# GSIOC.net
KiCad netlist of a schematic drawn in EAGLE
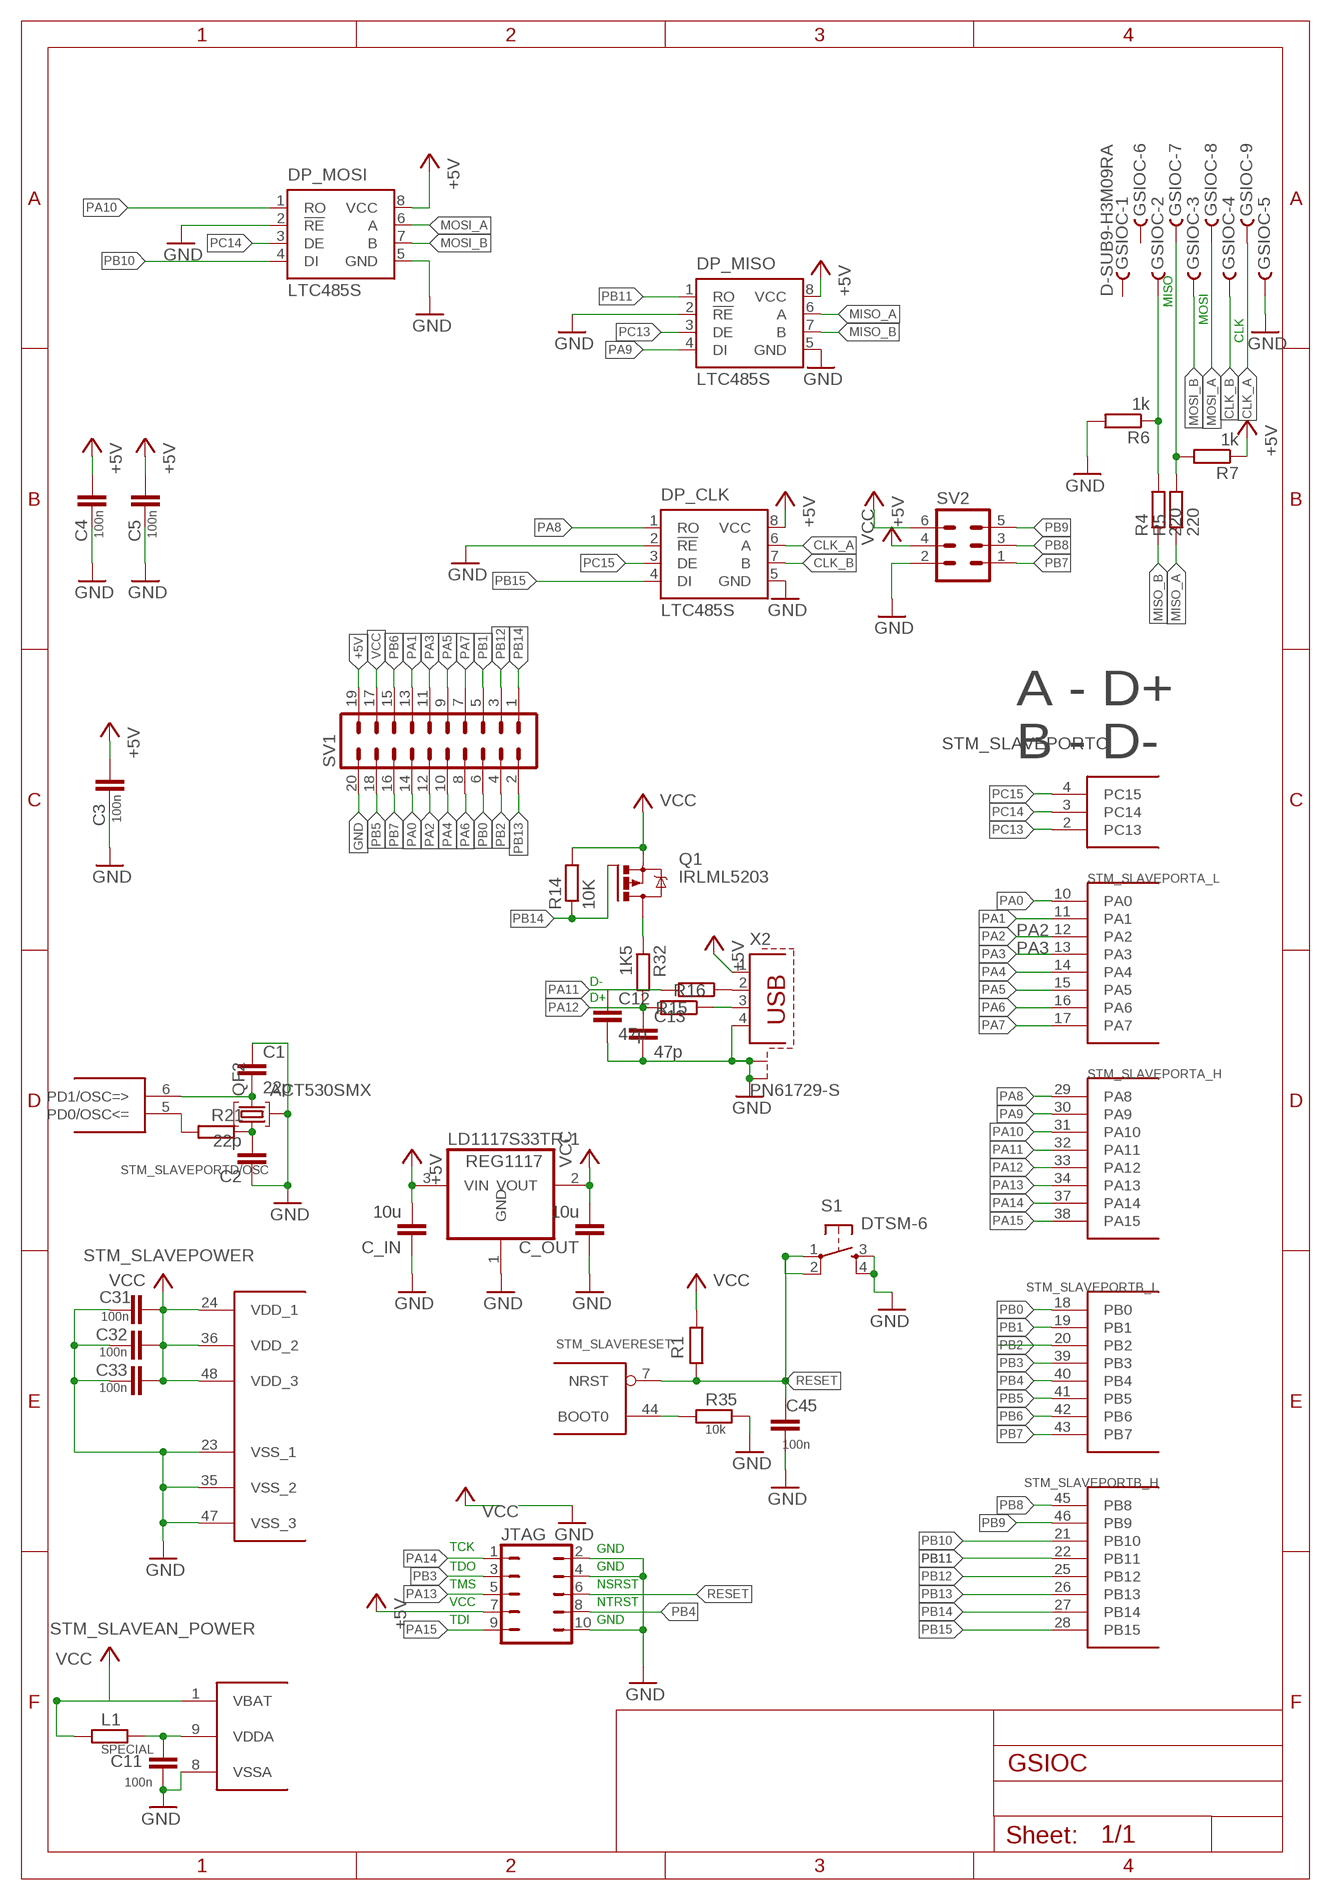
[diagram p0: schematic, sheet 1]

(export (version "E")
  (design (tool "Eeschema 10.0.6"))
  (components
    (comp (ref "C1")
      (value "22p")
      (footprint "eagle-import:C0805")
      (libsource (lib "eagle-import") (part "resistor_C-EUC0805"))
    )
    (comp (ref "C2")
      (value "22p")
      (footprint "eagle-import:C0805")
      (libsource (lib "eagle-import") (part "resistor_C-EUC0805"))
    )
    (comp (ref "C3")
      (value "100n")
      (footprint "eagle-import:C0805")
      (libsource (lib "eagle-import") (part "resistor_C-EUC0805"))
    )
    (comp (ref "C4")
      (value "100n")
      (footprint "eagle-import:C0805K")
      (libsource (lib "eagle-import") (part "C-EUC0805K"))
    )
    (comp (ref "C5")
      (value "100n")
      (footprint "eagle-import:C0805K")
      (libsource (lib "eagle-import") (part "C-EUC0805K"))
    )
    (comp (ref "C11")
      (value "100n")
      (footprint "eagle-import:C0805")
      (libsource (lib "eagle-import") (part "resistor_C-EUC0805"))
    )
    (comp (ref "C12")
      (value "47p")
      (footprint "eagle-import:C0805K")
      (libsource (lib "eagle-import") (part "C-EUC0805K"))
    )
    (comp (ref "C13")
      (value "47p")
      (footprint "eagle-import:C0805K")
      (libsource (lib "eagle-import") (part "C-EUC0805K"))
    )
    (comp (ref "C31")
      (value "100n")
      (footprint "eagle-import:C0805")
      (libsource (lib "eagle-import") (part "resistor_C-EUC0805"))
    )
    (comp (ref "C32")
      (value "100n")
      (footprint "eagle-import:C0805")
      (libsource (lib "eagle-import") (part "resistor_C-EUC0805"))
    )
    (comp (ref "C33")
      (value "100n")
      (footprint "eagle-import:C0805")
      (libsource (lib "eagle-import") (part "resistor_C-EUC0805"))
    )
    (comp (ref "C45")
      (value "100n")
      (footprint "eagle-import:C0805K")
      (libsource (lib "eagle-import") (part "C-EUC0805K"))
    )
    (comp (ref "C_IN")
      (value "10u")
      (footprint "eagle-import:C0805K")
      (libsource (lib "eagle-import") (part "C-EUC0805K"))
    )
    (comp (ref "C_OUT")
      (value "10u")
      (footprint "eagle-import:C0805K")
      (libsource (lib "eagle-import") (part "C-EUC0805K"))
    )
    (comp (ref "DP_CLK")
      (value "LTC485S")
      (footprint "eagle-import:SOIC8")
      (libsource (lib "eagle-import") (part "LTC485S"))
    )
    (comp (ref "DP_MISO")
      (value "LTC485S")
      (footprint "eagle-import:SOIC8")
      (libsource (lib "eagle-import") (part "LTC485S"))
    )
    (comp (ref "DP_MOSI")
      (value "LTC485S")
      (footprint "eagle-import:SOIC8")
      (libsource (lib "eagle-import") (part "LTC485S"))
    )
    (comp (ref "GSIOC")
      (value "D-SUB9-H3M09RA")
      (footprint "eagle-import:H3M09RA")
      (libsource (lib "eagle-import") (part "D-SUB9-H3M09RA"))
    )
    (comp (ref "JTAG")
      (value "JP5Q")
      (footprint "eagle-import:JP5Q")
      (libsource (lib "eagle-import") (part "JP5Q"))
    )
    (comp (ref "L1")
      (value "SPECIAL")
      (footprint "eagle-import:M0805")
      (libsource (lib "eagle-import") (part "R-EU_M0805"))
    )
    (comp (ref "LD1117S33TR-1")
      (value "REG1117")
      (footprint "eagle-import:SOT223")
      (libsource (lib "eagle-import") (part "REG1117"))
    )
    (comp (ref "Q1")
      (value "IRLML5203")
      (footprint "eagle-import:MICRO3")
      (libsource (lib "eagle-import") (part "IRLML5203"))
    )
    (comp (ref "QF2")
      (value "ACT530SMX")
      (footprint "eagle-import:ACT_530SMX")
      (libsource (lib "eagle-import") (part "ACT530SMX"))
    )
    (comp (ref "R1")
      (value "5k")
      (footprint "eagle-import:M0805")
      (libsource (lib "eagle-import") (part "R-EU_M0805"))
    )
    (comp (ref "R4")
      (value "220")
      (footprint "eagle-import:M0805")
      (libsource (lib "eagle-import") (part "R-EU_M0805"))
    )
    (comp (ref "R5")
      (value "220")
      (footprint "eagle-import:M0805")
      (libsource (lib "eagle-import") (part "R-EU_M0805"))
    )
    (comp (ref "R6")
      (value "1k")
      (footprint "eagle-import:M0805")
      (libsource (lib "eagle-import") (part "R-EU_M0805"))
    )
    (comp (ref "R7")
      (value "1k")
      (footprint "eagle-import:M0805")
      (libsource (lib "eagle-import") (part "R-EU_M0805"))
    )
    (comp (ref "R14")
      (value "10K")
      (footprint "eagle-import:M0805")
      (libsource (lib "eagle-import") (part "R-EU_M0805"))
    )
    (comp (ref "R15")
      (value "22")
      (footprint "eagle-import:M0805")
      (libsource (lib "eagle-import") (part "R-EU_M0805"))
    )
    (comp (ref "R16")
      (value "22")
      (footprint "eagle-import:M0805")
      (libsource (lib "eagle-import") (part "R-EU_M0805"))
    )
    (comp (ref "R21")
      (value "R-EU_M0805")
      (footprint "eagle-import:M0805")
      (libsource (lib "eagle-import") (part "R-EU_M0805"))
    )
    (comp (ref "R32")
      (value "1K5")
      (footprint "eagle-import:M0805")
      (libsource (lib "eagle-import") (part "R-EU_M0805"))
    )
    (comp (ref "R35")
      (value "10k")
      (footprint "eagle-import:M0805")
      (libsource (lib "eagle-import") (part "R-EU_M0805"))
    )
    (comp (ref "S1")
      (value "DTSM-6")
      (footprint "eagle-import:DTSM-6")
      (libsource (lib "eagle-import") (part "DTSM-6"))
    )
    (comp (ref "STM_SLAVE")
      (value "STM32F10XCXT6")
      (footprint "eagle-import:TQFP48")
      (libsource (lib "eagle-import") (part "STM32F10XCXT6"))
    )
    (comp (ref "SV1")
      (value "ML20L")
      (footprint "eagle-import:ML20L")
      (libsource (lib "eagle-import") (part "ML20L"))
    )
    (comp (ref "SV2")
      (value "ML6L")
      (footprint "eagle-import:ML6L")
      (libsource (lib "eagle-import") (part "ML6L"))
    )
    (comp (ref "X2")
      (value "PN61729-S")
      (footprint "eagle-import:PN61729-S")
      (libsource (lib "eagle-import") (part "PN61729-S"))
    )
  )
  (nets
    (net (code "1") (name "+5V") (class "Default")
      (node (ref "C3") (pin "1") (pinfunction "1_1") (pintype "passive"))
      (node (ref "C4") (pin "1") (pinfunction "1_1") (pintype "passive"))
      (node (ref "C5") (pin "1") (pinfunction "1_1") (pintype "passive"))
      (node (ref "C_IN") (pin "2") (pinfunction "2_2") (pintype "passive"))
      (node (ref "DP_CLK") (pin "8") (pinfunction "VCC_8") (pintype "input"))
      (node (ref "DP_MISO") (pin "8") (pinfunction "VCC_8") (pintype "input"))
      (node (ref "DP_MOSI") (pin "8") (pinfunction "VCC_8") (pintype "input"))
      (node (ref "JTAG") (pin "7") (pinfunction "7_7") (pintype "passive"))
      (node (ref "LD1117S33TR-1") (pin "3") (pinfunction "VIN_3") (pintype "input"))
      (node (ref "R7") (pin "1") (pinfunction "1_1") (pintype "passive"))
      (node (ref "SV1") (pin "19") (pinfunction "19_19") (pintype "passive"))
      (node (ref "SV2") (pin "6") (pinfunction "6_6") (pintype "passive"))
      (node (ref "X2") (pin "1") (pinfunction "1_1") (pintype "passive"))
    )
    (net (code "2") (name "CLK_A") (class "Default")
      (node (ref "DP_CLK") (pin "6") (pinfunction "A_6") (pintype "bidirectional"))
      (node (ref "GSIOC") (pin "9") (pinfunction "F_9") (pintype "passive"))
    )
    (net (code "3") (name "CLK_B") (class "Default")
      (node (ref "DP_CLK") (pin "7") (pinfunction "B_7") (pintype "bidirectional"))
      (node (ref "GSIOC") (pin "4") (pinfunction "F_4") (pintype "passive"))
    )
    (net (code "4") (name "GND") (class "Default")
      (node (ref "C1") (pin "1") (pinfunction "1_1") (pintype "passive"))
      (node (ref "C11") (pin "2") (pinfunction "2_2") (pintype "passive"))
      (node (ref "C12") (pin "2") (pinfunction "2_2") (pintype "passive"))
      (node (ref "C13") (pin "2") (pinfunction "2_2") (pintype "passive"))
      (node (ref "C2") (pin "1") (pinfunction "1_1") (pintype "passive"))
      (node (ref "C3") (pin "2") (pinfunction "2_2") (pintype "passive"))
      (node (ref "C31") (pin "2") (pinfunction "2_2") (pintype "passive"))
      (node (ref "C32") (pin "2") (pinfunction "2_2") (pintype "passive"))
      (node (ref "C33") (pin "2") (pinfunction "2_2") (pintype "passive"))
      (node (ref "C4") (pin "2") (pinfunction "2_2") (pintype "passive"))
      (node (ref "C45") (pin "2") (pinfunction "2_2") (pintype "passive"))
      (node (ref "C5") (pin "2") (pinfunction "2_2") (pintype "passive"))
      (node (ref "C_IN") (pin "1") (pinfunction "1_1") (pintype "passive"))
      (node (ref "C_OUT") (pin "1") (pinfunction "1_1") (pintype "passive"))
      (node (ref "DP_CLK") (pin "2") (pinfunction "~{RE}_2") (pintype "input"))
      (node (ref "DP_CLK") (pin "5") (pinfunction "GND_5") (pintype "input"))
      (node (ref "DP_MISO") (pin "2") (pinfunction "~{RE}_2") (pintype "input"))
      (node (ref "DP_MISO") (pin "5") (pinfunction "GND_5") (pintype "input"))
      (node (ref "DP_MOSI") (pin "2") (pinfunction "~{RE}_2") (pintype "input"))
      (node (ref "DP_MOSI") (pin "5") (pinfunction "GND_5") (pintype "input"))
      (node (ref "GSIOC") (pin "5") (pinfunction "F_5") (pintype "passive"))
      (node (ref "JTAG") (pin "10") (pinfunction "10_10") (pintype "passive"))
      (node (ref "JTAG") (pin "2") (pinfunction "2_2") (pintype "passive"))
      (node (ref "JTAG") (pin "4") (pinfunction "4_4") (pintype "passive"))
      (node (ref "LD1117S33TR-1") (pin "1") (pinfunction "GND_1") (pintype "power_in"))
      (node (ref "QF2") (pin "S$1") (pinfunction "SHLD_S$1") (pintype "passive"))
      (node (ref "QF2") (pin "S$2") (pinfunction "SHLD_S$2") (pintype "passive"))
      (node (ref "R35") (pin "2") (pinfunction "2_2") (pintype "passive"))
      (node (ref "R6") (pin "2") (pinfunction "2_2") (pintype "passive"))
      (node (ref "S1") (pin "3") (pinfunction "3_3") (pintype "passive"))
      (node (ref "S1") (pin "4") (pinfunction "4_4") (pintype "passive"))
      (node (ref "STM_SLAVE") (pin "23") (pinfunction "VSS_1_23") (pintype "power_in"))
      (node (ref "STM_SLAVE") (pin "35") (pinfunction "VSS_2_35") (pintype "power_in"))
      (node (ref "STM_SLAVE") (pin "47") (pinfunction "VSS_3_47") (pintype "power_in"))
      (node (ref "STM_SLAVE") (pin "8") (pinfunction "VSSA_8") (pintype "power_in"))
      (node (ref "SV1") (pin "20") (pinfunction "20_20") (pintype "passive"))
      (node (ref "SV2") (pin "2") (pinfunction "2_2") (pintype "passive"))
      (node (ref "X2") (pin "4") (pinfunction "4_4") (pintype "passive"))
      (node (ref "X2") (pin "S1") (pinfunction "S1_S1") (pintype "passive"))
      (node (ref "X2") (pin "S2") (pinfunction "S2_S2") (pintype "passive"))
    )
    (net (code "5") (name "MISO_A") (class "Default")
      (node (ref "DP_MISO") (pin "6") (pinfunction "A_6") (pintype "bidirectional"))
      (node (ref "R5") (pin "1") (pinfunction "1_1") (pintype "passive"))
    )
    (net (code "6") (name "MISO_B") (class "Default")
      (node (ref "DP_MISO") (pin "7") (pinfunction "B_7") (pintype "bidirectional"))
      (node (ref "R4") (pin "1") (pinfunction "1_1") (pintype "passive"))
    )
    (net (code "7") (name "MOSI_A") (class "Default")
      (node (ref "DP_MOSI") (pin "6") (pinfunction "A_6") (pintype "bidirectional"))
      (node (ref "GSIOC") (pin "8") (pinfunction "F_8") (pintype "passive"))
    )
    (net (code "8") (name "MOSI_B") (class "Default")
      (node (ref "DP_MOSI") (pin "7") (pinfunction "B_7") (pintype "bidirectional"))
      (node (ref "GSIOC") (pin "3") (pinfunction "F_3") (pintype "passive"))
    )
    (net (code "9") (name "Net-(GSIOCB-F)") (class "Default")
      (node (ref "GSIOC") (pin "2") (pinfunction "F_2") (pintype "passive"))
      (node (ref "R4") (pin "2") (pinfunction "2_2") (pintype "passive"))
      (node (ref "R6") (pin "1") (pinfunction "1_1") (pintype "passive"))
    )
    (net (code "10") (name "Net-(GSIOCG-F)") (class "Default")
      (node (ref "GSIOC") (pin "7") (pinfunction "F_7") (pintype "passive"))
      (node (ref "R5") (pin "2") (pinfunction "2_2") (pintype "passive"))
      (node (ref "R7") (pin "2") (pinfunction "2_2") (pintype "passive"))
    )
    (net (code "11") (name "Net-(Q1-D)") (class "Default")
      (node (ref "Q1") (pin "3") (pinfunction "D_3") (pintype "passive"))
      (node (ref "R32") (pin "1") (pinfunction "1_1") (pintype "passive"))
    )
    (net (code "12") (name "Net-(QF2-1)") (class "Default")
      (node (ref "C2") (pin "2") (pinfunction "2_2") (pintype "passive"))
      (node (ref "QF2") (pin "P1") (pinfunction "1_P1") (pintype "passive"))
      (node (ref "R21") (pin "1") (pinfunction "1_1") (pintype "passive"))
    )
    (net (code "13") (name "Net-(QF2-2)") (class "Default")
      (node (ref "C1") (pin "2") (pinfunction "2_2") (pintype "passive"))
      (node (ref "QF2") (pin "P2") (pinfunction "2_P2") (pintype "passive"))
      (node (ref "STM_SLAVE") (pin "6") (pinfunction "PD1/OSC=>_6") (pintype "bidirectional"))
    )
    (net (code "14") (name "Net-(R15-Pad1)") (class "Default")
      (node (ref "R15") (pin "1") (pinfunction "1_1") (pintype "passive"))
      (node (ref "X2") (pin "3") (pinfunction "3_3") (pintype "passive"))
    )
    (net (code "15") (name "Net-(R16-Pad1)") (class "Default")
      (node (ref "R16") (pin "1") (pinfunction "1_1") (pintype "passive"))
      (node (ref "X2") (pin "2") (pinfunction "2_2") (pintype "passive"))
    )
    (net (code "16") (name "Net-(STM_SLAVEA-VDDA)") (class "Default")
      (node (ref "C11") (pin "1") (pinfunction "1_1") (pintype "passive"))
      (node (ref "L1") (pin "2") (pinfunction "2_2") (pintype "passive"))
      (node (ref "STM_SLAVE") (pin "9") (pinfunction "VDDA_9") (pintype "power_in"))
    )
    (net (code "17") (name "Net-(STM_SLAVEG-PD0{slash}OSC<=)") (class "Default")
      (node (ref "R21") (pin "2") (pinfunction "2_2") (pintype "passive"))
      (node (ref "STM_SLAVE") (pin "5") (pinfunction "PD0/OSC<=_5") (pintype "bidirectional"))
    )
    (net (code "18") (name "Net-(STM_SLAVEI-BOOT0)") (class "Default")
      (node (ref "R35") (pin "1") (pinfunction "1_1") (pintype "passive"))
      (node (ref "STM_SLAVE") (pin "44") (pinfunction "BOOT0_44") (pintype "input"))
    )
    (net (code "19") (name "PA0") (class "Default")
      (node (ref "STM_SLAVE") (pin "10") (pinfunction "PA0_10") (pintype "bidirectional"))
      (node (ref "SV1") (pin "14") (pinfunction "14_14") (pintype "passive"))
    )
    (net (code "20") (name "PA1") (class "Default")
      (node (ref "STM_SLAVE") (pin "11") (pinfunction "PA1_11") (pintype "bidirectional"))
      (node (ref "SV1") (pin "13") (pinfunction "13_13") (pintype "passive"))
    )
    (net (code "21") (name "PA2") (class "Default")
      (node (ref "STM_SLAVE") (pin "12") (pinfunction "PA2_12") (pintype "bidirectional"))
      (node (ref "SV1") (pin "12") (pinfunction "12_12") (pintype "passive"))
    )
    (net (code "22") (name "PA3") (class "Default")
      (node (ref "STM_SLAVE") (pin "13") (pinfunction "PA3_13") (pintype "bidirectional"))
      (node (ref "SV1") (pin "11") (pinfunction "11_11") (pintype "passive"))
    )
    (net (code "23") (name "PA4") (class "Default")
      (node (ref "STM_SLAVE") (pin "14") (pinfunction "PA4_14") (pintype "bidirectional"))
      (node (ref "SV1") (pin "10") (pinfunction "10_10") (pintype "passive"))
    )
    (net (code "24") (name "PA5") (class "Default")
      (node (ref "STM_SLAVE") (pin "15") (pinfunction "PA5_15") (pintype "bidirectional"))
      (node (ref "SV1") (pin "9") (pinfunction "9_9") (pintype "passive"))
    )
    (net (code "25") (name "PA6") (class "Default")
      (node (ref "STM_SLAVE") (pin "16") (pinfunction "PA6_16") (pintype "bidirectional"))
      (node (ref "SV1") (pin "8") (pinfunction "8_8") (pintype "passive"))
    )
    (net (code "26") (name "PA7") (class "Default")
      (node (ref "STM_SLAVE") (pin "17") (pinfunction "PA7_17") (pintype "bidirectional"))
      (node (ref "SV1") (pin "7") (pinfunction "7_7") (pintype "passive"))
    )
    (net (code "27") (name "PA8") (class "Default")
      (node (ref "DP_CLK") (pin "1") (pinfunction "RO_1") (pintype "output"))
      (node (ref "STM_SLAVE") (pin "29") (pinfunction "PA8_29") (pintype "bidirectional"))
    )
    (net (code "28") (name "PA9") (class "Default")
      (node (ref "DP_MISO") (pin "4") (pinfunction "DI_4") (pintype "input"))
      (node (ref "STM_SLAVE") (pin "30") (pinfunction "PA9_30") (pintype "bidirectional"))
    )
    (net (code "29") (name "PA10") (class "Default")
      (node (ref "DP_MOSI") (pin "1") (pinfunction "RO_1") (pintype "output"))
      (node (ref "STM_SLAVE") (pin "31") (pinfunction "PA10_31") (pintype "bidirectional"))
    )
    (net (code "30") (name "PA11") (class "Default")
      (node (ref "C12") (pin "1") (pinfunction "1_1") (pintype "passive"))
      (node (ref "R16") (pin "2") (pinfunction "2_2") (pintype "passive"))
      (node (ref "STM_SLAVE") (pin "32") (pinfunction "PA11_32") (pintype "bidirectional"))
    )
    (net (code "31") (name "PA12") (class "Default")
      (node (ref "C13") (pin "1") (pinfunction "1_1") (pintype "passive"))
      (node (ref "R15") (pin "2") (pinfunction "2_2") (pintype "passive"))
      (node (ref "R32") (pin "2") (pinfunction "2_2") (pintype "passive"))
      (node (ref "STM_SLAVE") (pin "33") (pinfunction "PA12_33") (pintype "bidirectional"))
    )
    (net (code "32") (name "PA13") (class "Default")
      (node (ref "JTAG") (pin "5") (pinfunction "5_5") (pintype "passive"))
      (node (ref "STM_SLAVE") (pin "34") (pinfunction "PA13_34") (pintype "bidirectional"))
    )
    (net (code "33") (name "PA14") (class "Default")
      (node (ref "JTAG") (pin "1") (pinfunction "1_1") (pintype "passive"))
      (node (ref "STM_SLAVE") (pin "37") (pinfunction "PA14_37") (pintype "bidirectional"))
    )
    (net (code "34") (name "PA15") (class "Default")
      (node (ref "JTAG") (pin "9") (pinfunction "9_9") (pintype "passive"))
      (node (ref "STM_SLAVE") (pin "38") (pinfunction "PA15_38") (pintype "bidirectional"))
    )
    (net (code "35") (name "PB0") (class "Default")
      (node (ref "STM_SLAVE") (pin "18") (pinfunction "PB0_18") (pintype "bidirectional"))
      (node (ref "SV1") (pin "6") (pinfunction "6_6") (pintype "passive"))
    )
    (net (code "36") (name "PB1") (class "Default")
      (node (ref "STM_SLAVE") (pin "19") (pinfunction "PB1_19") (pintype "bidirectional"))
      (node (ref "SV1") (pin "5") (pinfunction "5_5") (pintype "passive"))
    )
    (net (code "37") (name "PB2") (class "Default")
      (node (ref "STM_SLAVE") (pin "20") (pinfunction "PB2_20") (pintype "bidirectional"))
      (node (ref "SV1") (pin "4") (pinfunction "4_4") (pintype "passive"))
    )
    (net (code "38") (name "PB3") (class "Default")
      (node (ref "JTAG") (pin "3") (pinfunction "3_3") (pintype "passive"))
      (node (ref "STM_SLAVE") (pin "39") (pinfunction "PB3_39") (pintype "bidirectional"))
    )
    (net (code "39") (name "PB4") (class "Default")
      (node (ref "JTAG") (pin "8") (pinfunction "8_8") (pintype "passive"))
      (node (ref "STM_SLAVE") (pin "40") (pinfunction "PB4_40") (pintype "bidirectional"))
    )
    (net (code "40") (name "PB5") (class "Default")
      (node (ref "STM_SLAVE") (pin "41") (pinfunction "PB5_41") (pintype "bidirectional"))
      (node (ref "SV1") (pin "18") (pinfunction "18_18") (pintype "passive"))
    )
    (net (code "41") (name "PB6") (class "Default")
      (node (ref "STM_SLAVE") (pin "42") (pinfunction "PB6_42") (pintype "bidirectional"))
      (node (ref "SV1") (pin "15") (pinfunction "15_15") (pintype "passive"))
    )
    (net (code "42") (name "PB7") (class "Default")
      (node (ref "STM_SLAVE") (pin "43") (pinfunction "PB7_43") (pintype "bidirectional"))
      (node (ref "SV1") (pin "16") (pinfunction "16_16") (pintype "passive"))
      (node (ref "SV2") (pin "1") (pinfunction "1_1") (pintype "passive"))
    )
    (net (code "43") (name "PB8") (class "Default")
      (node (ref "STM_SLAVE") (pin "45") (pinfunction "PB8_45") (pintype "bidirectional"))
      (node (ref "SV2") (pin "3") (pinfunction "3_3") (pintype "passive"))
    )
    (net (code "44") (name "PB9") (class "Default")
      (node (ref "STM_SLAVE") (pin "46") (pinfunction "PB9_46") (pintype "bidirectional"))
      (node (ref "SV2") (pin "5") (pinfunction "5_5") (pintype "passive"))
    )
    (net (code "45") (name "PB10") (class "Default")
      (node (ref "DP_MOSI") (pin "4") (pinfunction "DI_4") (pintype "input"))
      (node (ref "STM_SLAVE") (pin "21") (pinfunction "PB10_21") (pintype "bidirectional"))
    )
    (net (code "46") (name "PB11") (class "Default")
      (node (ref "DP_MISO") (pin "1") (pinfunction "RO_1") (pintype "output"))
      (node (ref "STM_SLAVE") (pin "22") (pinfunction "PB11_22") (pintype "bidirectional"))
    )
    (net (code "47") (name "PB12") (class "Default")
      (node (ref "STM_SLAVE") (pin "25") (pinfunction "PB12_25") (pintype "bidirectional"))
      (node (ref "SV1") (pin "3") (pinfunction "3_3") (pintype "passive"))
    )
    (net (code "48") (name "PB13") (class "Default")
      (node (ref "STM_SLAVE") (pin "26") (pinfunction "PB13_26") (pintype "bidirectional"))
      (node (ref "SV1") (pin "2") (pinfunction "2_2") (pintype "passive"))
    )
    (net (code "49") (name "PB14") (class "Default")
      (node (ref "Q1") (pin "1") (pinfunction "G_1") (pintype "passive"))
      (node (ref "R14") (pin "1") (pinfunction "1_1") (pintype "passive"))
      (node (ref "STM_SLAVE") (pin "27") (pinfunction "PB14_27") (pintype "bidirectional"))
      (node (ref "SV1") (pin "1") (pinfunction "1_1") (pintype "passive"))
    )
    (net (code "50") (name "PB15") (class "Default")
      (node (ref "DP_CLK") (pin "4") (pinfunction "DI_4") (pintype "input"))
      (node (ref "STM_SLAVE") (pin "28") (pinfunction "PB15_28") (pintype "bidirectional"))
    )
    (net (code "51") (name "PC13") (class "Default")
      (node (ref "DP_MISO") (pin "3") (pinfunction "DE_3") (pintype "input"))
      (node (ref "STM_SLAVE") (pin "2") (pinfunction "PC13_2") (pintype "bidirectional"))
    )
    (net (code "52") (name "PC14") (class "Default")
      (node (ref "DP_MOSI") (pin "3") (pinfunction "DE_3") (pintype "input"))
      (node (ref "STM_SLAVE") (pin "3") (pinfunction "PC14_3") (pintype "bidirectional"))
    )
    (net (code "53") (name "PC15") (class "Default")
      (node (ref "DP_CLK") (pin "3") (pinfunction "DE_3") (pintype "input"))
      (node (ref "STM_SLAVE") (pin "4") (pinfunction "PC15_4") (pintype "bidirectional"))
    )
    (net (code "54") (name "RESET") (class "Default")
      (node (ref "C45") (pin "1") (pinfunction "1_1") (pintype "passive"))
      (node (ref "JTAG") (pin "6") (pinfunction "6_6") (pintype "passive"))
      (node (ref "R1") (pin "2") (pinfunction "2_2") (pintype "passive"))
      (node (ref "S1") (pin "1") (pinfunction "1_1") (pintype "passive"))
      (node (ref "S1") (pin "2") (pinfunction "2_2") (pintype "passive"))
      (node (ref "STM_SLAVE") (pin "7") (pinfunction "NRST_7") (pintype "input"))
    )
    (net (code "55") (name "VCC") (class "Default")
      (node (ref "C31") (pin "1") (pinfunction "1_1") (pintype "passive"))
      (node (ref "C32") (pin "1") (pinfunction "1_1") (pintype "passive"))
      (node (ref "C33") (pin "1") (pinfunction "1_1") (pintype "passive"))
      (node (ref "C_OUT") (pin "2") (pinfunction "2_2") (pintype "passive"))
      (node (ref "L1") (pin "1") (pinfunction "1_1") (pintype "passive"))
      (node (ref "LD1117S33TR-1") (pin "2") (pinfunction "VOUT_2") (pintype "output"))
      (node (ref "Q1") (pin "2") (pinfunction "S_2") (pintype "passive"))
      (node (ref "R1") (pin "1") (pinfunction "1_1") (pintype "passive"))
      (node (ref "R14") (pin "2") (pinfunction "2_2") (pintype "passive"))
      (node (ref "STM_SLAVE") (pin "1") (pinfunction "VBAT_1") (pintype "power_in"))
      (node (ref "STM_SLAVE") (pin "24") (pinfunction "VDD_1_24") (pintype "power_in"))
      (node (ref "STM_SLAVE") (pin "36") (pinfunction "VDD_2_36") (pintype "power_in"))
      (node (ref "STM_SLAVE") (pin "48") (pinfunction "VDD_3_48") (pintype "power_in"))
      (node (ref "SV1") (pin "17") (pinfunction "17_17") (pintype "passive"))
      (node (ref "SV2") (pin "4") (pinfunction "4_4") (pintype "passive"))
    )
    (net (code "56") (name "unconnected-(GSIOCA-F-Pad1)") (class "Default")
      (node (ref "GSIOC") (pin "1") (pinfunction "F_1") (pintype "passive"))
    )
    (net (code "57") (name "unconnected-(GSIOCF-F-Pad6)") (class "Default")
      (node (ref "GSIOC") (pin "6") (pinfunction "F_6") (pintype "passive"))
    )
  )
)
